# Bolt.net
KiCad netlist of a schematic drawn in EAGLE
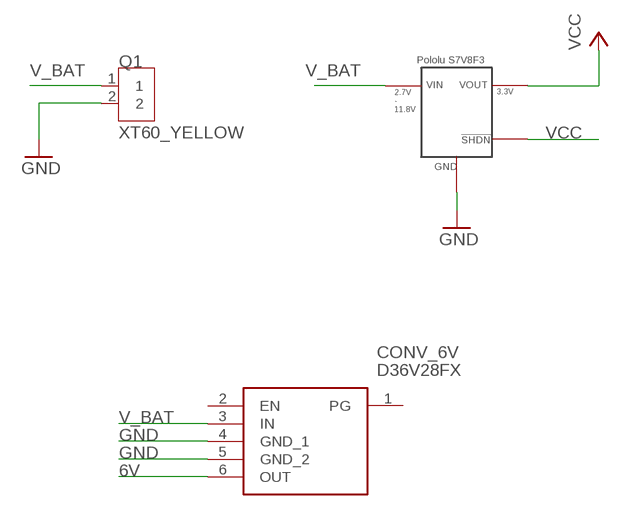
[diagram p0: schematic, sheet 1]
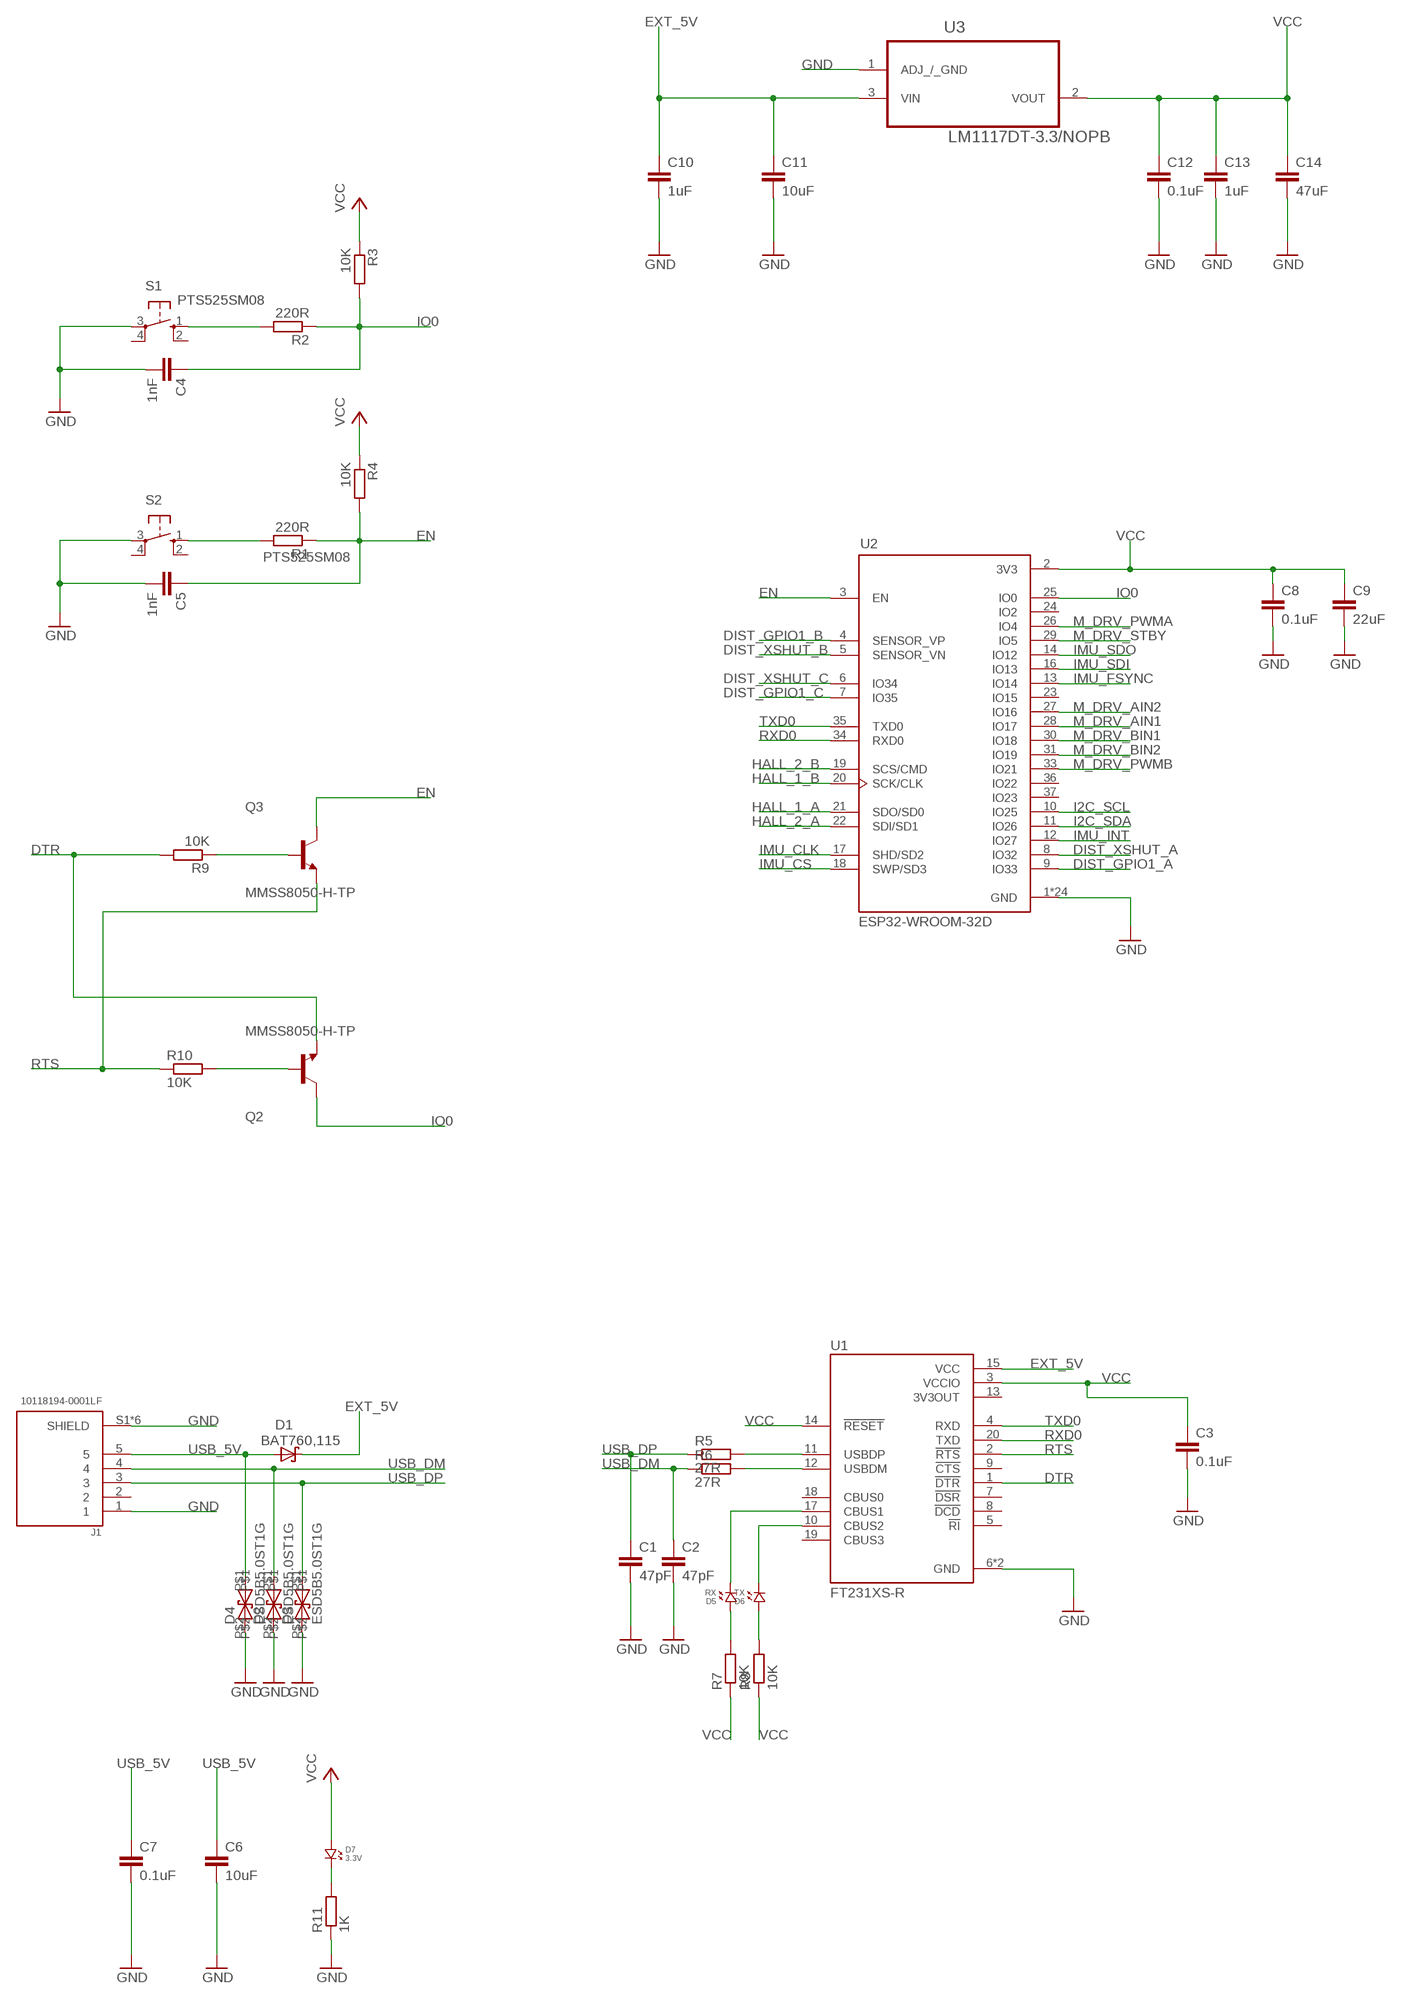
[diagram p1: schematic, sheet 2]
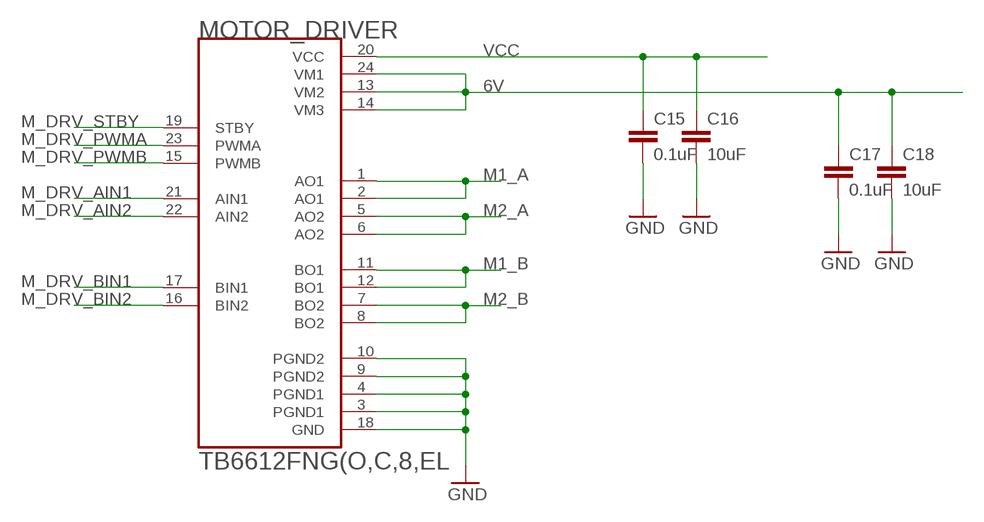
[diagram p2: schematic, sheet 3]
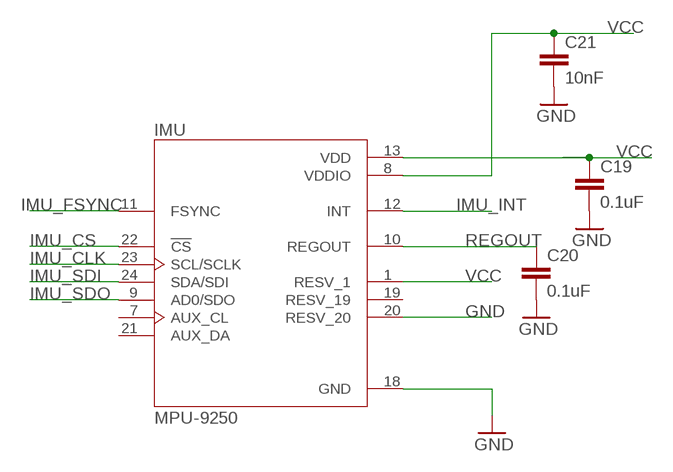
[diagram p3: schematic, sheet 4]
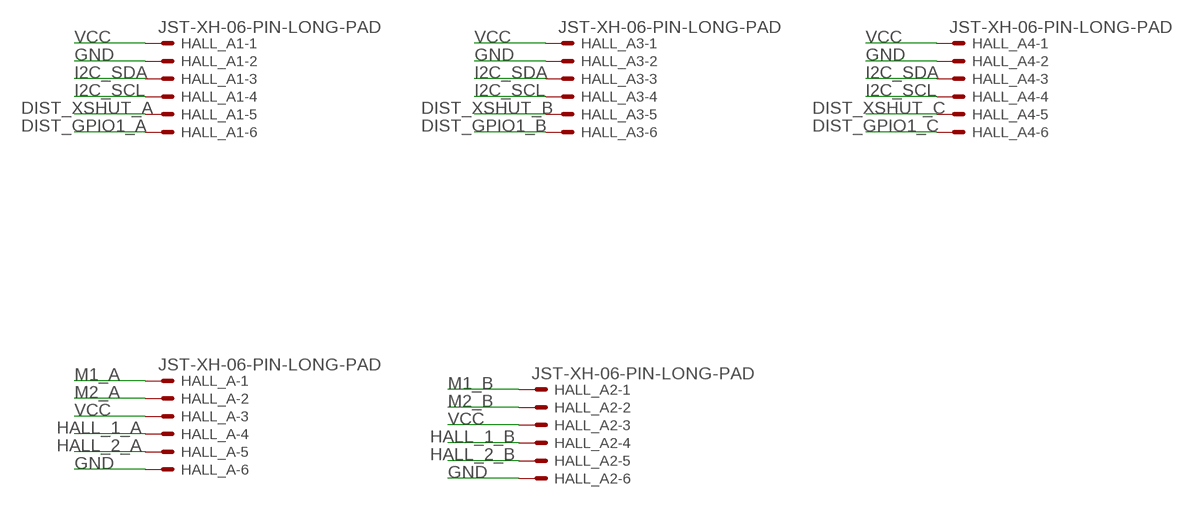
[diagram p4: schematic, sheet 5]

(export (version "E")
  (design (tool "Eeschema 10.0.6"))
  (components
    (comp (ref "CONV_3V3")
      (value "S7V8F3")
      (footprint "eagle-import:S7V8F3")
      (libsource (lib "eagle-import") (part "S7V8F3"))
    )
    (comp (ref "CONV_6V")
      (value "D36V28FX")
      (footprint "eagle-import:D36V28FX")
      (libsource (lib "eagle-import") (part "D36V28FX"))
    )
    (comp (ref "Q1")
      (value "XT60_YELLOW")
      (footprint "eagle-import:AMASS_XT60PB-M")
      (fields (field (name "MF") "Pololu") (field (name "MP") "XT60 YELLOW"))
      (libsource (lib "eagle-import") (part "XT60_YELLOW"))
    )
    (comp (ref "C1")
      (value "47pF")
      (footprint "eagle-import:C0805K")
      (libsource (lib "eagle-import") (part "C-EUC0805K"))
    )
    (comp (ref "C2")
      (value "47pF")
      (footprint "eagle-import:C0805K")
      (libsource (lib "eagle-import") (part "C-EUC0805K"))
    )
    (comp (ref "C3")
      (value "0.1uF")
      (footprint "eagle-import:C0805K")
      (libsource (lib "eagle-import") (part "C-EUC0805K"))
    )
    (comp (ref "C4")
      (value "1nF")
      (footprint "eagle-import:C0805K")
      (libsource (lib "eagle-import") (part "C-EUC0805K"))
    )
    (comp (ref "C5")
      (value "1nF")
      (footprint "eagle-import:C0805K")
      (libsource (lib "eagle-import") (part "C-EUC0805K"))
    )
    (comp (ref "C6")
      (value "10uF")
      (footprint "eagle-import:C0805K")
      (libsource (lib "eagle-import") (part "C-EUC0805K"))
    )
    (comp (ref "C7")
      (value "0.1uF")
      (footprint "eagle-import:C0805K")
      (libsource (lib "eagle-import") (part "C-EUC0805K"))
    )
    (comp (ref "C8")
      (value "0.1uF")
      (footprint "eagle-import:C0805K")
      (libsource (lib "eagle-import") (part "C-EUC0805K"))
    )
    (comp (ref "C9")
      (value "22uF")
      (footprint "eagle-import:C0805K")
      (libsource (lib "eagle-import") (part "C-EUC0805K"))
    )
    (comp (ref "C10")
      (value "1uF")
      (footprint "eagle-import:C0805K")
      (libsource (lib "eagle-import") (part "C-EUC0805K"))
    )
    (comp (ref "C11")
      (value "10uF")
      (footprint "eagle-import:C0805K")
      (libsource (lib "eagle-import") (part "C-EUC0805K"))
    )
    (comp (ref "C12")
      (value "0.1uF")
      (footprint "eagle-import:C0805K")
      (libsource (lib "eagle-import") (part "C-EUC0805K"))
    )
    (comp (ref "C13")
      (value "1uF")
      (footprint "eagle-import:C0805K")
      (libsource (lib "eagle-import") (part "C-EUC0805K"))
    )
    (comp (ref "C14")
      (value "47uF")
      (footprint "eagle-import:C0805K")
      (libsource (lib "eagle-import") (part "C-EUC0805K"))
    )
    (comp (ref "D1")
      (value "BAT760,115")
      (footprint "eagle-import:SOD323(F)")
      (fields (field (name "MF") "Nexperia USA"))
      (libsource (lib "eagle-import") (part "BAT760,115"))
    )
    (comp (ref "D2")
      (value "ESD5B5.0ST1G")
      (footprint "eagle-import:SOD-523")
      (fields (field (name "MF") "Nexperia USA") (field (name "MP") "BAT760,115"))
      (libsource (lib "eagle-import") (part "ESD5B5.0ST1G"))
    )
    (comp (ref "D3")
      (value "ESD5B5.0ST1G")
      (footprint "eagle-import:SOD-523")
      (fields (field (name "MF") "Nexperia USA") (field (name "MP") "BAT760,115"))
      (libsource (lib "eagle-import") (part "ESD5B5.0ST1G"))
    )
    (comp (ref "D4")
      (value "ESD5B5.0ST1G")
      (footprint "eagle-import:SOD-523")
      (fields (field (name "MF") "Nexperia USA") (field (name "MP") "BAT760,115"))
      (libsource (lib "eagle-import") (part "ESD5B5.0ST1G"))
    )
    (comp (ref "D5")
      (value "RX")
      (footprint "eagle-import:0805.LED")
      (libsource (lib "eagle-import") (part "LED.0805"))
    )
    (comp (ref "D6")
      (value "TX")
      (footprint "eagle-import:0805.LED")
      (libsource (lib "eagle-import") (part "LED.0805"))
    )
    (comp (ref "D7")
      (value "3.3V")
      (footprint "eagle-import:0805.LED")
      (libsource (lib "eagle-import") (part "LED.0805"))
    )
    (comp (ref "J1")
      (value "10118194-0001LF")
      (footprint "eagle-import:AMPHENOL_10118194-0001LF")
      (fields (field (name "MF") "Amphenol ICC (FCI)"))
      (libsource (lib "eagle-import") (part "10118194-0001LF"))
    )
    (comp (ref "Q2")
      (value "MMSS8050-H-TP")
      (footprint "eagle-import:TRANS_MMSS8050-H-TP")
      (fields (field (name "MF") "Micro Commercial"))
      (libsource (lib "eagle-import") (part "MMSS8050-H-TP"))
    )
    (comp (ref "Q3")
      (value "MMSS8050-H-TP")
      (footprint "eagle-import:TRANS_MMSS8050-H-TP")
      (fields (field (name "MF") "Micro Commercial"))
      (libsource (lib "eagle-import") (part "MMSS8050-H-TP"))
    )
    (comp (ref "R1")
      (value "220R")
      (footprint "eagle-import:R0805")
      (libsource (lib "eagle-import") (part "R-EU_R0805"))
    )
    (comp (ref "R2")
      (value "220R")
      (footprint "eagle-import:R0805")
      (libsource (lib "eagle-import") (part "R-EU_R0805"))
    )
    (comp (ref "R3")
      (value "10K")
      (footprint "eagle-import:R0805")
      (libsource (lib "eagle-import") (part "R-EU_R0805"))
    )
    (comp (ref "R4")
      (value "10K")
      (footprint "eagle-import:R0805")
      (libsource (lib "eagle-import") (part "R-EU_R0805"))
    )
    (comp (ref "R5")
      (value "27R")
      (footprint "eagle-import:R0805")
      (libsource (lib "eagle-import") (part "R-EU_R0805"))
    )
    (comp (ref "R6")
      (value "27R")
      (footprint "eagle-import:R0805")
      (libsource (lib "eagle-import") (part "R-EU_R0805"))
    )
    (comp (ref "R7")
      (value "10K")
      (footprint "eagle-import:R0805")
      (libsource (lib "eagle-import") (part "R-EU_R0805"))
    )
    (comp (ref "R8")
      (value "10K")
      (footprint "eagle-import:R0805")
      (libsource (lib "eagle-import") (part "R-EU_R0805"))
    )
    (comp (ref "R9")
      (value "10K")
      (footprint "eagle-import:R0805")
      (libsource (lib "eagle-import") (part "R-EU_R0805"))
    )
    (comp (ref "R10")
      (value "10K")
      (footprint "eagle-import:R0805")
      (libsource (lib "eagle-import") (part "R-EU_R0805"))
    )
    (comp (ref "R11")
      (value "1K")
      (footprint "eagle-import:R0805")
      (libsource (lib "eagle-import") (part "R-EU_R0805"))
    )
    (comp (ref "S1")
      (value "PTS525SM08")
      (footprint "eagle-import:SM08")
      (fields (field (name "MF") "C&K Components") (field (name "MPN") "PTS525SM08SMTR2LFS"))
      (libsource (lib "eagle-import") (part "PTS52508SM"))
    )
    (comp (ref "S2")
      (value "PTS525SM08")
      (footprint "eagle-import:SM08")
      (fields (field (name "MF") "C&K Components") (field (name "MPN") "PTS525SM08SMTR2LFS"))
      (libsource (lib "eagle-import") (part "PTS52508SM"))
    )
    (comp (ref "U1")
      (value "FT231XS-R")
      (footprint "eagle-import:SOP63P599X175-20N")
      (fields (field (name "DIGI-KEY_PART_NUMBER") "768-1129-1-ND") (field (name "MF") "FTDI,"))
      (libsource (lib "eagle-import") (part "FT231XS-R"))
    )
    (comp (ref "U2")
      (value "ESP32-WROOM-32D")
      (footprint "eagle-import:MODULE_ESP32-WROOM-32D")
      (fields (field (name "MF") "Espressif Systems"))
      (libsource (lib "eagle-import") (part "ESP32-WROOM-32D"))
    )
    (comp (ref "U3")
      (value "LM1117DT-3.3/NOPB")
      (footprint "eagle-import:TO228P970X238-3N")
      (fields (field (name "MF") "Texas Instruments"))
      (libsource (lib "eagle-import") (part "LM1117DT-3.3/NOPB"))
    )
    (comp (ref "C15")
      (value "0.1uF")
      (footprint "eagle-import:C0805K")
      (libsource (lib "eagle-import") (part "C-EUC0805K"))
    )
    (comp (ref "C16")
      (value "10uF")
      (footprint "eagle-import:C0805K")
      (libsource (lib "eagle-import") (part "C-EUC0805K"))
    )
    (comp (ref "C17")
      (value "0.1uF")
      (footprint "eagle-import:C0805K")
      (libsource (lib "eagle-import") (part "C-EUC0805K"))
    )
    (comp (ref "C18")
      (value "10uF")
      (footprint "eagle-import:C0805K")
      (libsource (lib "eagle-import") (part "C-EUC0805K"))
    )
    (comp (ref "MOTOR_DRIVER")
      (value "TB6612FNG(O,C,8,EL")
      (footprint "eagle-import:SOP65P760X160-24N")
      (fields (field (name "MF") "Toshiba"))
      (libsource (lib "eagle-import") (part "TB6612FNG(O,C,8,EL"))
    )
    (comp (ref "C19")
      (value "0.1uF")
      (footprint "eagle-import:C0805K")
      (libsource (lib "eagle-import") (part "C-EUC0805K"))
    )
    (comp (ref "C20")
      (value "0.1uF")
      (footprint "eagle-import:C0805K")
      (libsource (lib "eagle-import") (part "C-EUC0805K"))
    )
    (comp (ref "C21")
      (value "10nF")
      (footprint "eagle-import:C0805K")
      (libsource (lib "eagle-import") (part "C-EUC0805K"))
    )
    (comp (ref "IMU")
      (value "MPU-9250")
      (footprint "eagle-import:QFN40P300X300X105-24N")
      (fields (field (name "MF") "TDK InvenSense"))
      (libsource (lib "eagle-import") (part "MPU-9250"))
    )
    (comp (ref "HALL_A")
      (value "JST-XH-06-PIN-LONG-PAD")
      (footprint "eagle-import:JST-XH-06-PACKAGE-LONG-PAD")
      (libsource (lib "eagle-import") (part "JST-XH-06-PIN-LONG-PAD"))
    )
    (comp (ref "HALL_A1")
      (value "JST-XH-06-PIN-LONG-PAD")
      (footprint "eagle-import:JST-XH-06-PACKAGE-LONG-PAD")
      (libsource (lib "eagle-import") (part "JST-XH-06-PIN-LONG-PAD"))
    )
    (comp (ref "HALL_A2")
      (value "JST-XH-06-PIN-LONG-PAD")
      (footprint "eagle-import:JST-XH-06-PACKAGE-LONG-PAD")
      (libsource (lib "eagle-import") (part "JST-XH-06-PIN-LONG-PAD"))
    )
    (comp (ref "HALL_A3")
      (value "JST-XH-06-PIN-LONG-PAD")
      (footprint "eagle-import:JST-XH-06-PACKAGE-LONG-PAD")
      (libsource (lib "eagle-import") (part "JST-XH-06-PIN-LONG-PAD"))
    )
    (comp (ref "HALL_A4")
      (value "JST-XH-06-PIN-LONG-PAD")
      (footprint "eagle-import:JST-XH-06-PACKAGE-LONG-PAD")
      (libsource (lib "eagle-import") (part "JST-XH-06-PIN-LONG-PAD"))
    )
  )
  (nets
    (net (code "1") (name "3V3OUT") (class "Default")
      (node (ref "U1") (pin "13") (pinfunction "3V3OUT_13") (pintype "power_in"))
    )
    (net (code "2") (name "6V") (class "Default")
      (node (ref "C17") (pin "1") (pinfunction "1_1") (pintype "passive"))
      (node (ref "C18") (pin "1") (pinfunction "1_1") (pintype "passive"))
      (node (ref "CONV_6V") (pin "6") (pinfunction "OUT_6") (pintype "bidirectional"))
      (node (ref "MOTOR_DRIVER") (pin "13") (pinfunction "VM2_13") (pintype "power_in"))
      (node (ref "MOTOR_DRIVER") (pin "14") (pinfunction "VM3_14") (pintype "power_in"))
      (node (ref "MOTOR_DRIVER") (pin "24") (pinfunction "VM1_24") (pintype "power_in"))
    )
    (net (code "3") (name "DIST_GPIO1_A") (class "Default")
      (node (ref "HALL_A1") (pin "6") (pinfunction "S_6") (pintype "passive"))
      (node (ref "U2") (pin "9") (pinfunction "IO33_9") (pintype "bidirectional"))
    )
    (net (code "4") (name "DIST_GPIO1_B") (class "Default")
      (node (ref "HALL_A3") (pin "6") (pinfunction "S_6") (pintype "passive"))
      (node (ref "U2") (pin "4") (pinfunction "SENSOR_VP_4") (pintype "input"))
    )
    (net (code "5") (name "DIST_GPIO1_C") (class "Default")
      (node (ref "HALL_A4") (pin "6") (pinfunction "S_6") (pintype "passive"))
      (node (ref "U2") (pin "7") (pinfunction "IO35_7") (pintype "input"))
    )
    (net (code "6") (name "DIST_XSHUT_A") (class "Default")
      (node (ref "HALL_A1") (pin "5") (pinfunction "S_5") (pintype "passive"))
      (node (ref "U2") (pin "8") (pinfunction "IO32_8") (pintype "bidirectional"))
    )
    (net (code "7") (name "DIST_XSHUT_B") (class "Default")
      (node (ref "HALL_A3") (pin "5") (pinfunction "S_5") (pintype "passive"))
      (node (ref "U2") (pin "5") (pinfunction "SENSOR_VN_5") (pintype "input"))
    )
    (net (code "8") (name "DIST_XSHUT_C") (class "Default")
      (node (ref "HALL_A4") (pin "5") (pinfunction "S_5") (pintype "passive"))
      (node (ref "U2") (pin "6") (pinfunction "IO34_6") (pintype "input"))
    )
    (net (code "9") (name "DTR") (class "Default")
      (node (ref "Q2") (pin "2") (pinfunction "E_2") (pintype "passive"))
      (node (ref "R9") (pin "2") (pinfunction "2_2") (pintype "passive"))
      (node (ref "U1") (pin "1") (pinfunction "~{DTR}_1") (pintype "output"))
    )
    (net (code "10") (name "EN") (class "Default")
      (node (ref "C5") (pin "1") (pinfunction "1_1") (pintype "passive"))
      (node (ref "Q3") (pin "3") (pinfunction "C_3") (pintype "passive"))
      (node (ref "R1") (pin "1") (pinfunction "1_1") (pintype "passive"))
      (node (ref "R4") (pin "2") (pinfunction "2_2") (pintype "passive"))
      (node (ref "U2") (pin "3") (pinfunction "EN_3") (pintype "input"))
    )
    (net (code "11") (name "EXT_5V") (class "Default")
      (node (ref "C10") (pin "1") (pinfunction "1_1") (pintype "passive"))
      (node (ref "C11") (pin "1") (pinfunction "1_1") (pintype "passive"))
      (node (ref "D1") (pin "1") (pinfunction "K_1") (pintype "passive"))
      (node (ref "U1") (pin "15") (pinfunction "VCC_15") (pintype "power_in"))
      (node (ref "U3") (pin "3") (pinfunction "VIN_3") (pintype "input"))
    )
    (net (code "12") (name "GND") (class "Default")
      (node (ref "C1") (pin "2") (pinfunction "2_2") (pintype "passive"))
      (node (ref "C10") (pin "2") (pinfunction "2_2") (pintype "passive"))
      (node (ref "C11") (pin "2") (pinfunction "2_2") (pintype "passive"))
      (node (ref "C12") (pin "2") (pinfunction "2_2") (pintype "passive"))
      (node (ref "C13") (pin "2") (pinfunction "2_2") (pintype "passive"))
      (node (ref "C14") (pin "2") (pinfunction "2_2") (pintype "passive"))
      (node (ref "C15") (pin "2") (pinfunction "2_2") (pintype "passive"))
      (node (ref "C16") (pin "2") (pinfunction "2_2") (pintype "passive"))
      (node (ref "C17") (pin "2") (pinfunction "2_2") (pintype "passive"))
      (node (ref "C18") (pin "2") (pinfunction "2_2") (pintype "passive"))
      (node (ref "C19") (pin "2") (pinfunction "2_2") (pintype "passive"))
      (node (ref "C2") (pin "2") (pinfunction "2_2") (pintype "passive"))
      (node (ref "C20") (pin "2") (pinfunction "2_2") (pintype "passive"))
      (node (ref "C21") (pin "2") (pinfunction "2_2") (pintype "passive"))
      (node (ref "C3") (pin "2") (pinfunction "2_2") (pintype "passive"))
      (node (ref "C4") (pin "2") (pinfunction "2_2") (pintype "passive"))
      (node (ref "C5") (pin "2") (pinfunction "2_2") (pintype "passive"))
      (node (ref "C6") (pin "2") (pinfunction "2_2") (pintype "passive"))
      (node (ref "C7") (pin "2") (pinfunction "2_2") (pintype "passive"))
      (node (ref "C8") (pin "2") (pinfunction "2_2") (pintype "passive"))
      (node (ref "C9") (pin "2") (pinfunction "2_2") (pintype "passive"))
      (node (ref "CONV_3V3") (pin "GND") (pinfunction "GND_GND") (pintype "bidirectional"))
      (node (ref "CONV_6V") (pin "4") (pinfunction "GND_1_4") (pintype "bidirectional"))
      (node (ref "CONV_6V") (pin "5") (pinfunction "GND_2_5") (pintype "bidirectional"))
      (node (ref "D2") (pin "P$2") (pinfunction "P$1_P$2") (pintype "bidirectional"))
      (node (ref "D3") (pin "P$2") (pinfunction "P$1_P$2") (pintype "bidirectional"))
      (node (ref "D4") (pin "P$2") (pinfunction "P$1_P$2") (pintype "bidirectional"))
      (node (ref "HALL_A") (pin "6") (pinfunction "S_6") (pintype "passive"))
      (node (ref "HALL_A1") (pin "2") (pinfunction "S_2") (pintype "passive"))
      (node (ref "HALL_A2") (pin "6") (pinfunction "S_6") (pintype "passive"))
      (node (ref "HALL_A3") (pin "2") (pinfunction "S_2") (pintype "passive"))
      (node (ref "HALL_A4") (pin "2") (pinfunction "S_2") (pintype "passive"))
      (node (ref "IMU") (pin "18") (pinfunction "GND_18") (pintype "power_in"))
      (node (ref "IMU") (pin "20") (pinfunction "RESV_20_20") (pintype "passive"))
      (node (ref "J1") (pin "1") (pinfunction "1_1") (pintype "passive"))
      (node (ref "J1") (pin "S1") (pinfunction "SHIELD_S1") (pintype "passive"))
      (node (ref "J1") (pin "S2") (pinfunction "SHIELD_S2") (pintype "passive"))
      (node (ref "J1") (pin "S3") (pinfunction "SHIELD_S3") (pintype "passive"))
      (node (ref "J1") (pin "S4") (pinfunction "SHIELD_S4") (pintype "passive"))
      (node (ref "J1") (pin "S5") (pinfunction "SHIELD_S5") (pintype "passive"))
      (node (ref "J1") (pin "S6") (pinfunction "SHIELD_S6") (pintype "passive"))
      (node (ref "MOTOR_DRIVER") (pin "10") (pinfunction "PGND2_10") (pintype "passive"))
      (node (ref "MOTOR_DRIVER") (pin "18") (pinfunction "GND_18") (pintype "passive"))
      (node (ref "MOTOR_DRIVER") (pin "3") (pinfunction "PGND1_3") (pintype "passive"))
      (node (ref "MOTOR_DRIVER") (pin "4") (pinfunction "PGND1_4") (pintype "passive"))
      (node (ref "MOTOR_DRIVER") (pin "9") (pinfunction "PGND2_9") (pintype "passive"))
      (node (ref "Q1") (pin "2") (pinfunction "2_2") (pintype "passive"))
      (node (ref "R11") (pin "1") (pinfunction "1_1") (pintype "passive"))
      (node (ref "S1") (pin "3") (pinfunction "P_3") (pintype "passive"))
      (node (ref "S2") (pin "3") (pinfunction "P_3") (pintype "passive"))
      (node (ref "U1") (pin "16") (pinfunction "GND_16") (pintype "power_in"))
      (node (ref "U1") (pin "6") (pinfunction "GND_6") (pintype "power_in"))
      (node (ref "U2") (pin "1") (pinfunction "GND_1") (pintype "power_in"))
      (node (ref "U2") (pin "15") (pinfunction "GND_15") (pintype "power_in"))
      (node (ref "U2") (pin "38") (pinfunction "GND_38") (pintype "power_in"))
      (node (ref "U2") (pin "39_1") (pinfunction "GND_39_1") (pintype "power_in"))
      (node (ref "U2") (pin "39_10") (pinfunction "GND_39_10") (pintype "power_in"))
      (node (ref "U2") (pin "39_11") (pinfunction "GND_39_11") (pintype "power_in"))
      (node (ref "U2") (pin "39_12") (pinfunction "GND_39_12") (pintype "power_in"))
      (node (ref "U2") (pin "39_13") (pinfunction "GND_39_13") (pintype "power_in"))
      (node (ref "U2") (pin "39_14") (pinfunction "GND_39_14") (pintype "power_in"))
      (node (ref "U2") (pin "39_15") (pinfunction "GND_39_15") (pintype "power_in"))
      (node (ref "U2") (pin "39_16") (pinfunction "GND_39_16") (pintype "power_in"))
      (node (ref "U2") (pin "39_17") (pinfunction "GND_39_17") (pintype "power_in"))
      (node (ref "U2") (pin "39_18") (pinfunction "GND_39_18") (pintype "power_in"))
      (node (ref "U2") (pin "39_19") (pinfunction "GND_39_19") (pintype "power_in"))
      (node (ref "U2") (pin "39_2") (pinfunction "GND_39_2") (pintype "power_in"))
      (node (ref "U2") (pin "39_20") (pinfunction "GND_39_20") (pintype "power_in"))
      (node (ref "U2") (pin "39_21") (pinfunction "GND_39_21") (pintype "power_in"))
      (node (ref "U2") (pin "39_3") (pinfunction "GND_39_3") (pintype "power_in"))
      (node (ref "U2") (pin "39_4") (pinfunction "GND_39_4") (pintype "power_in"))
      (node (ref "U2") (pin "39_5") (pinfunction "GND_39_5") (pintype "power_in"))
      (node (ref "U2") (pin "39_6") (pinfunction "GND_39_6") (pintype "power_in"))
      (node (ref "U2") (pin "39_7") (pinfunction "GND_39_7") (pintype "power_in"))
      (node (ref "U2") (pin "39_8") (pinfunction "GND_39_8") (pintype "power_in"))
      (node (ref "U2") (pin "39_9") (pinfunction "GND_39_9") (pintype "power_in"))
      (node (ref "U3") (pin "1") (pinfunction "ADJ_/_GND_1") (pintype "power_in"))
    )
    (net (code "13") (name "HALL_1_A") (class "Default")
      (node (ref "HALL_A") (pin "4") (pinfunction "S_4") (pintype "passive"))
      (node (ref "U2") (pin "21") (pinfunction "SDO/SD0_21") (pintype "bidirectional"))
    )
    (net (code "14") (name "HALL_1_B") (class "Default")
      (node (ref "HALL_A2") (pin "4") (pinfunction "S_4") (pintype "passive"))
      (node (ref "U2") (pin "20") (pinfunction "SCK/CLK_20") (pintype "bidirectional"))
    )
    (net (code "15") (name "HALL_2_A") (class "Default")
      (node (ref "HALL_A") (pin "5") (pinfunction "S_5") (pintype "passive"))
      (node (ref "U2") (pin "22") (pinfunction "SDI/SD1_22") (pintype "bidirectional"))
    )
    (net (code "16") (name "HALL_2_B") (class "Default")
      (node (ref "HALL_A2") (pin "5") (pinfunction "S_5") (pintype "passive"))
      (node (ref "U2") (pin "19") (pinfunction "SCS/CMD_19") (pintype "bidirectional"))
    )
    (net (code "17") (name "I2C_SCL") (class "Default")
      (node (ref "HALL_A1") (pin "4") (pinfunction "S_4") (pintype "passive"))
      (node (ref "HALL_A3") (pin "4") (pinfunction "S_4") (pintype "passive"))
      (node (ref "HALL_A4") (pin "4") (pinfunction "S_4") (pintype "passive"))
      (node (ref "U2") (pin "10") (pinfunction "IO25_10") (pintype "bidirectional"))
    )
    (net (code "18") (name "I2C_SDA") (class "Default")
      (node (ref "HALL_A1") (pin "3") (pinfunction "S_3") (pintype "passive"))
      (node (ref "HALL_A3") (pin "3") (pinfunction "S_3") (pintype "passive"))
      (node (ref "HALL_A4") (pin "3") (pinfunction "S_3") (pintype "passive"))
      (node (ref "U2") (pin "11") (pinfunction "IO26_11") (pintype "bidirectional"))
    )
    (net (code "19") (name "IMU_CLK") (class "Default")
      (node (ref "IMU") (pin "23") (pinfunction "SCL/SCLK_23") (pintype "input"))
      (node (ref "U2") (pin "17") (pinfunction "SHD/SD2_17") (pintype "bidirectional"))
    )
    (net (code "20") (name "IMU_CS") (class "Default")
      (node (ref "IMU") (pin "22") (pinfunction "~{CS}_22") (pintype "input"))
      (node (ref "U2") (pin "18") (pinfunction "SWP/SD3_18") (pintype "bidirectional"))
    )
    (net (code "21") (name "IMU_FSYNC") (class "Default")
      (node (ref "IMU") (pin "11") (pinfunction "FSYNC_11") (pintype "input"))
      (node (ref "U2") (pin "13") (pinfunction "IO14_13") (pintype "bidirectional"))
    )
    (net (code "22") (name "IMU_INT") (class "Default")
      (node (ref "IMU") (pin "12") (pinfunction "INT_12") (pintype "output"))
      (node (ref "U2") (pin "12") (pinfunction "IO27_12") (pintype "bidirectional"))
    )
    (net (code "23") (name "IMU_SDI") (class "Default")
      (node (ref "IMU") (pin "24") (pinfunction "SDA/SDI_24") (pintype "bidirectional"))
      (node (ref "U2") (pin "16") (pinfunction "IO13_16") (pintype "bidirectional"))
    )
    (net (code "24") (name "IMU_SDO") (class "Default")
      (node (ref "IMU") (pin "9") (pinfunction "AD0/SDO_9") (pintype "output"))
      (node (ref "U2") (pin "14") (pinfunction "IO12_14") (pintype "bidirectional"))
    )
    (net (code "25") (name "IO0") (class "Default")
      (node (ref "C4") (pin "1") (pinfunction "1_1") (pintype "passive"))
      (node (ref "Q2") (pin "3") (pinfunction "C_3") (pintype "passive"))
      (node (ref "R2") (pin "1") (pinfunction "1_1") (pintype "passive"))
      (node (ref "R3") (pin "2") (pinfunction "2_2") (pintype "passive"))
      (node (ref "U2") (pin "25") (pinfunction "IO0_25") (pintype "bidirectional"))
    )
    (net (code "26") (name "M1_A") (class "Default")
      (node (ref "HALL_A") (pin "1") (pinfunction "S_1") (pintype "passive"))
      (node (ref "MOTOR_DRIVER") (pin "1") (pinfunction "AO1_1") (pintype "output"))
      (node (ref "MOTOR_DRIVER") (pin "2") (pinfunction "AO1_2") (pintype "output"))
    )
    (net (code "27") (name "M1_B") (class "Default")
      (node (ref "HALL_A2") (pin "1") (pinfunction "S_1") (pintype "passive"))
      (node (ref "MOTOR_DRIVER") (pin "11") (pinfunction "BO1_11") (pintype "output"))
      (node (ref "MOTOR_DRIVER") (pin "12") (pinfunction "BO1_12") (pintype "output"))
    )
    (net (code "28") (name "M2_A") (class "Default")
      (node (ref "HALL_A") (pin "2") (pinfunction "S_2") (pintype "passive"))
      (node (ref "MOTOR_DRIVER") (pin "5") (pinfunction "AO2_5") (pintype "output"))
      (node (ref "MOTOR_DRIVER") (pin "6") (pinfunction "AO2_6") (pintype "output"))
    )
    (net (code "29") (name "M2_B") (class "Default")
      (node (ref "HALL_A2") (pin "2") (pinfunction "S_2") (pintype "passive"))
      (node (ref "MOTOR_DRIVER") (pin "7") (pinfunction "BO2_7") (pintype "output"))
      (node (ref "MOTOR_DRIVER") (pin "8") (pinfunction "BO2_8") (pintype "output"))
    )
    (net (code "30") (name "M_DRV_AIN1") (class "Default")
      (node (ref "MOTOR_DRIVER") (pin "21") (pinfunction "AIN1_21") (pintype "input"))
      (node (ref "U2") (pin "28") (pinfunction "IO17_28") (pintype "bidirectional"))
    )
    (net (code "31") (name "M_DRV_AIN2") (class "Default")
      (node (ref "MOTOR_DRIVER") (pin "22") (pinfunction "AIN2_22") (pintype "input"))
      (node (ref "U2") (pin "27") (pinfunction "IO16_27") (pintype "bidirectional"))
    )
    (net (code "32") (name "M_DRV_BIN1") (class "Default")
      (node (ref "MOTOR_DRIVER") (pin "17") (pinfunction "BIN1_17") (pintype "input"))
      (node (ref "U2") (pin "30") (pinfunction "IO18_30") (pintype "bidirectional"))
    )
    (net (code "33") (name "M_DRV_BIN2") (class "Default")
      (node (ref "MOTOR_DRIVER") (pin "16") (pinfunction "BIN2_16") (pintype "input"))
      (node (ref "U2") (pin "31") (pinfunction "IO19_31") (pintype "bidirectional"))
    )
    (net (code "34") (name "M_DRV_PWMA") (class "Default")
      (node (ref "MOTOR_DRIVER") (pin "23") (pinfunction "PWMA_23") (pintype "input"))
      (node (ref "U2") (pin "26") (pinfunction "IO4_26") (pintype "bidirectional"))
    )
    (net (code "35") (name "M_DRV_PWMB") (class "Default")
      (node (ref "MOTOR_DRIVER") (pin "15") (pinfunction "PWMB_15") (pintype "input"))
      (node (ref "U2") (pin "33") (pinfunction "IO21_33") (pintype "bidirectional"))
    )
    (net (code "36") (name "M_DRV_STBY") (class "Default")
      (node (ref "MOTOR_DRIVER") (pin "19") (pinfunction "STBY_19") (pintype "input"))
      (node (ref "U2") (pin "29") (pinfunction "IO5_29") (pintype "bidirectional"))
    )
    (net (code "37") (name "Net-(D5-1)") (class "Default")
      (node (ref "D5") (pin "P$1") (pinfunction "1_P$1") (pintype "bidirectional"))
      (node (ref "R7") (pin "2") (pinfunction "2_2") (pintype "passive"))
    )
    (net (code "38") (name "Net-(D5-2)") (class "Default")
      (node (ref "D5") (pin "P$2") (pinfunction "2_P$2") (pintype "bidirectional"))
      (node (ref "U1") (pin "17") (pinfunction "CBUS1_17") (pintype "bidirectional"))
    )
    (net (code "39") (name "Net-(D6-1)") (class "Default")
      (node (ref "D6") (pin "P$1") (pinfunction "1_P$1") (pintype "bidirectional"))
      (node (ref "R8") (pin "2") (pinfunction "2_2") (pintype "passive"))
    )
    (net (code "40") (name "Net-(D6-2)") (class "Default")
      (node (ref "D6") (pin "P$2") (pinfunction "2_P$2") (pintype "bidirectional"))
      (node (ref "U1") (pin "10") (pinfunction "CBUS2_10") (pintype "bidirectional"))
    )
    (net (code "41") (name "Net-(D7-2)") (class "Default")
      (node (ref "D7") (pin "P$2") (pinfunction "2_P$2") (pintype "bidirectional"))
      (node (ref "R11") (pin "2") (pinfunction "2_2") (pintype "passive"))
    )
    (net (code "42") (name "Net-(Q2-B)") (class "Default")
      (node (ref "Q2") (pin "1") (pinfunction "B_1") (pintype "passive"))
      (node (ref "R10") (pin "2") (pinfunction "2_2") (pintype "passive"))
    )
    (net (code "43") (name "Net-(Q3-B)") (class "Default")
      (node (ref "Q3") (pin "1") (pinfunction "B_1") (pintype "passive"))
      (node (ref "R9") (pin "1") (pinfunction "1_1") (pintype "passive"))
    )
    (net (code "44") (name "Net-(R1-Pad2)") (class "Default")
      (node (ref "R1") (pin "2") (pinfunction "2_2") (pintype "passive"))
      (node (ref "S2") (pin "1") (pinfunction "S_1") (pintype "passive"))
    )
    (net (code "45") (name "Net-(R2-Pad2)") (class "Default")
      (node (ref "R2") (pin "2") (pinfunction "2_2") (pintype "passive"))
      (node (ref "S1") (pin "1") (pinfunction "S_1") (pintype "passive"))
    )
    (net (code "46") (name "Net-(U1-USBDM)") (class "Default")
      (node (ref "R6") (pin "2") (pinfunction "2_2") (pintype "passive"))
      (node (ref "U1") (pin "12") (pinfunction "USBDM_12") (pintype "input"))
    )
    (net (code "47") (name "Net-(U1-USBDP)") (class "Default")
      (node (ref "R5") (pin "2") (pinfunction "2_2") (pintype "passive"))
      (node (ref "U1") (pin "11") (pinfunction "USBDP_11") (pintype "input"))
    )
    (net (code "48") (name "REGOUT") (class "Default")
      (node (ref "C20") (pin "1") (pinfunction "1_1") (pintype "passive"))
      (node (ref "IMU") (pin "10") (pinfunction "REGOUT_10") (pintype "output"))
    )
    (net (code "49") (name "RTS") (class "Default")
      (node (ref "Q3") (pin "2") (pinfunction "E_2") (pintype "passive"))
      (node (ref "R10") (pin "1") (pinfunction "1_1") (pintype "passive"))
      (node (ref "U1") (pin "2") (pinfunction "~{RTS}_2") (pintype "output"))
    )
    (net (code "50") (name "RXD0") (class "Default")
      (node (ref "U1") (pin "20") (pinfunction "TXD_20") (pintype "output"))
      (node (ref "U2") (pin "34") (pinfunction "RXD0_34") (pintype "bidirectional"))
    )
    (net (code "51") (name "TXD0") (class "Default")
      (node (ref "U1") (pin "4") (pinfunction "RXD_4") (pintype "input"))
      (node (ref "U2") (pin "35") (pinfunction "TXD0_35") (pintype "bidirectional"))
    )
    (net (code "52") (name "USB_5V") (class "Default")
      (node (ref "C6") (pin "1") (pinfunction "1_1") (pintype "passive"))
      (node (ref "C7") (pin "1") (pinfunction "1_1") (pintype "passive"))
      (node (ref "D1") (pin "2") (pinfunction "A_2") (pintype "passive"))
      (node (ref "D4") (pin "P$1") (pinfunction "P$2_P$1") (pintype "bidirectional"))
      (node (ref "J1") (pin "5") (pinfunction "5_5") (pintype "passive"))
    )
    (net (code "53") (name "USB_DM") (class "Default")
      (node (ref "C2") (pin "1") (pinfunction "1_1") (pintype "passive"))
      (node (ref "D2") (pin "P$1") (pinfunction "P$2_P$1") (pintype "bidirectional"))
      (node (ref "J1") (pin "4") (pinfunction "4_4") (pintype "passive"))
      (node (ref "R6") (pin "1") (pinfunction "1_1") (pintype "passive"))
    )
    (net (code "54") (name "USB_DP") (class "Default")
      (node (ref "C1") (pin "1") (pinfunction "1_1") (pintype "passive"))
      (node (ref "D3") (pin "P$1") (pinfunction "P$2_P$1") (pintype "bidirectional"))
      (node (ref "J1") (pin "3") (pinfunction "3_3") (pintype "passive"))
      (node (ref "R5") (pin "1") (pinfunction "1_1") (pintype "passive"))
    )
    (net (code "55") (name "VCC") (class "Default")
      (node (ref "C12") (pin "1") (pinfunction "1_1") (pintype "passive"))
      (node (ref "C13") (pin "1") (pinfunction "1_1") (pintype "passive"))
      (node (ref "C14") (pin "1") (pinfunction "1_1") (pintype "passive"))
      (node (ref "C15") (pin "1") (pinfunction "1_1") (pintype "passive"))
      (node (ref "C16") (pin "1") (pinfunction "1_1") (pintype "passive"))
      (node (ref "C19") (pin "1") (pinfunction "1_1") (pintype "passive"))
      (node (ref "C21") (pin "1") (pinfunction "1_1") (pintype "passive"))
      (node (ref "C3") (pin "1") (pinfunction "1_1") (pintype "passive"))
      (node (ref "C8") (pin "1") (pinfunction "1_1") (pintype "passive"))
      (node (ref "C9") (pin "1") (pinfunction "1_1") (pintype "passive"))
      (node (ref "CONV_3V3") (pin "!SHDN") (pinfunction "~{SHDN}_!SHDN") (pintype "bidirectional"))
      (node (ref "CONV_3V3") (pin "VOUT") (pinfunction "VOUT_VOUT") (pintype "bidirectional"))
      (node (ref "D7") (pin "P$1") (pinfunction "1_P$1") (pintype "bidirectional"))
      (node (ref "HALL_A") (pin "3") (pinfunction "S_3") (pintype "passive"))
      (node (ref "HALL_A1") (pin "1") (pinfunction "S_1") (pintype "passive"))
      (node (ref "HALL_A2") (pin "3") (pinfunction "S_3") (pintype "passive"))
      (node (ref "HALL_A3") (pin "1") (pinfunction "S_1") (pintype "passive"))
      (node (ref "HALL_A4") (pin "1") (pinfunction "S_1") (pintype "passive"))
      (node (ref "IMU") (pin "1") (pinfunction "RESV_1_1") (pintype "passive"))
      (node (ref "IMU") (pin "13") (pinfunction "VDD_13") (pintype "power_in"))
      (node (ref "IMU") (pin "8") (pinfunction "VDDIO_8") (pintype "power_in"))
      (node (ref "MOTOR_DRIVER") (pin "20") (pinfunction "VCC_20") (pintype "power_in"))
      (node (ref "R3") (pin "1") (pinfunction "1_1") (pintype "passive"))
      (node (ref "R4") (pin "1") (pinfunction "1_1") (pintype "passive"))
      (node (ref "R7") (pin "1") (pinfunction "1_1") (pintype "passive"))
      (node (ref "R8") (pin "1") (pinfunction "1_1") (pintype "passive"))
      (node (ref "U1") (pin "14") (pinfunction "~{RESET}_14") (pintype "input"))
      (node (ref "U1") (pin "3") (pinfunction "VCCIO_3") (pintype "power_in"))
      (node (ref "U2") (pin "2") (pinfunction "3V3_2") (pintype "power_in"))
      (node (ref "U3") (pin "2") (pinfunction "VOUT_2") (pintype "output"))
    )
    (net (code "56") (name "V_BAT") (class "Default")
      (node (ref "CONV_3V3") (pin "VIN") (pinfunction "VIN_VIN") (pintype "bidirectional"))
      (node (ref "CONV_6V") (pin "3") (pinfunction "IN_3") (pintype "bidirectional"))
      (node (ref "Q1") (pin "1") (pinfunction "1_1") (pintype "passive"))
    )
    (net (code "57") (name "unconnected-(CONV_6V-EN-Pad2)") (class "Default")
      (node (ref "CONV_6V") (pin "2") (pinfunction "EN_2") (pintype "bidirectional"))
    )
    (net (code "58") (name "unconnected-(CONV_6V-PG-Pad1)") (class "Default")
      (node (ref "CONV_6V") (pin "1") (pinfunction "PG_1") (pintype "bidirectional"))
    )
    (net (code "59") (name "unconnected-(IMU-AUX_CL-Pad7)") (class "Default")
      (node (ref "IMU") (pin "7") (pinfunction "AUX_CL_7") (pintype "input"))
    )
    (net (code "60") (name "unconnected-(IMU-AUX_DA-Pad21)") (class "Default")
      (node (ref "IMU") (pin "21") (pinfunction "AUX_DA_21") (pintype "input"))
    )
    (net (code "61") (name "unconnected-(IMU-RESV_19-Pad19)") (class "Default")
      (node (ref "IMU") (pin "19") (pinfunction "RESV_19_19") (pintype "passive"))
    )
    (net (code "62") (name "unconnected-(J1-Pad2)") (class "Default")
      (node (ref "J1") (pin "2") (pinfunction "2_2") (pintype "passive"))
    )
    (net (code "63") (name "unconnected-(S1-P-Pad4)") (class "Default")
      (node (ref "S1") (pin "4") (pinfunction "P_4") (pintype "passive"))
    )
    (net (code "64") (name "unconnected-(S1-S-Pad2)") (class "Default")
      (node (ref "S1") (pin "2") (pinfunction "S_2") (pintype "passive"))
    )
    (net (code "65") (name "unconnected-(S2-P-Pad4)") (class "Default")
      (node (ref "S2") (pin "4") (pinfunction "P_4") (pintype "passive"))
    )
    (net (code "66") (name "unconnected-(S2-S-Pad2)") (class "Default")
      (node (ref "S2") (pin "2") (pinfunction "S_2") (pintype "passive"))
    )
    (net (code "67") (name "unconnected-(U1-CBUS0-Pad18)") (class "Default")
      (node (ref "U1") (pin "18") (pinfunction "CBUS0_18") (pintype "bidirectional"))
    )
    (net (code "68") (name "unconnected-(U1-CBUS3-Pad19)") (class "Default")
      (node (ref "U1") (pin "19") (pinfunction "CBUS3_19") (pintype "bidirectional"))
    )
    (net (code "69") (name "unconnected-(U1-~{CTS}-Pad9)") (class "Default")
      (node (ref "U1") (pin "9") (pinfunction "~{CTS}_9") (pintype "input"))
    )
    (net (code "70") (name "unconnected-(U1-~{DCD}-Pad8)") (class "Default")
      (node (ref "U1") (pin "8") (pinfunction "~{DCD}_8") (pintype "input"))
    )
    (net (code "71") (name "unconnected-(U1-~{DSR}-Pad7)") (class "Default")
      (node (ref "U1") (pin "7") (pinfunction "~{DSR}_7") (pintype "input"))
    )
    (net (code "72") (name "unconnected-(U1-~{RI}-Pad5)") (class "Default")
      (node (ref "U1") (pin "5") (pinfunction "~{RI}_5") (pintype "input"))
    )
    (net (code "73") (name "unconnected-(U2-IO2-Pad24)") (class "Default")
      (node (ref "U2") (pin "24") (pinfunction "IO2_24") (pintype "bidirectional"))
    )
    (net (code "74") (name "unconnected-(U2-IO15-Pad23)") (class "Default")
      (node (ref "U2") (pin "23") (pinfunction "IO15_23") (pintype "bidirectional"))
    )
    (net (code "75") (name "unconnected-(U2-IO22-Pad36)") (class "Default")
      (node (ref "U2") (pin "36") (pinfunction "IO22_36") (pintype "bidirectional"))
    )
    (net (code "76") (name "unconnected-(U2-IO23-Pad37)") (class "Default")
      (node (ref "U2") (pin "37") (pinfunction "IO23_37") (pintype "bidirectional"))
    )
  )
)
